# 12db-Xover.net
KiCad netlist of a schematic drawn in EAGLE
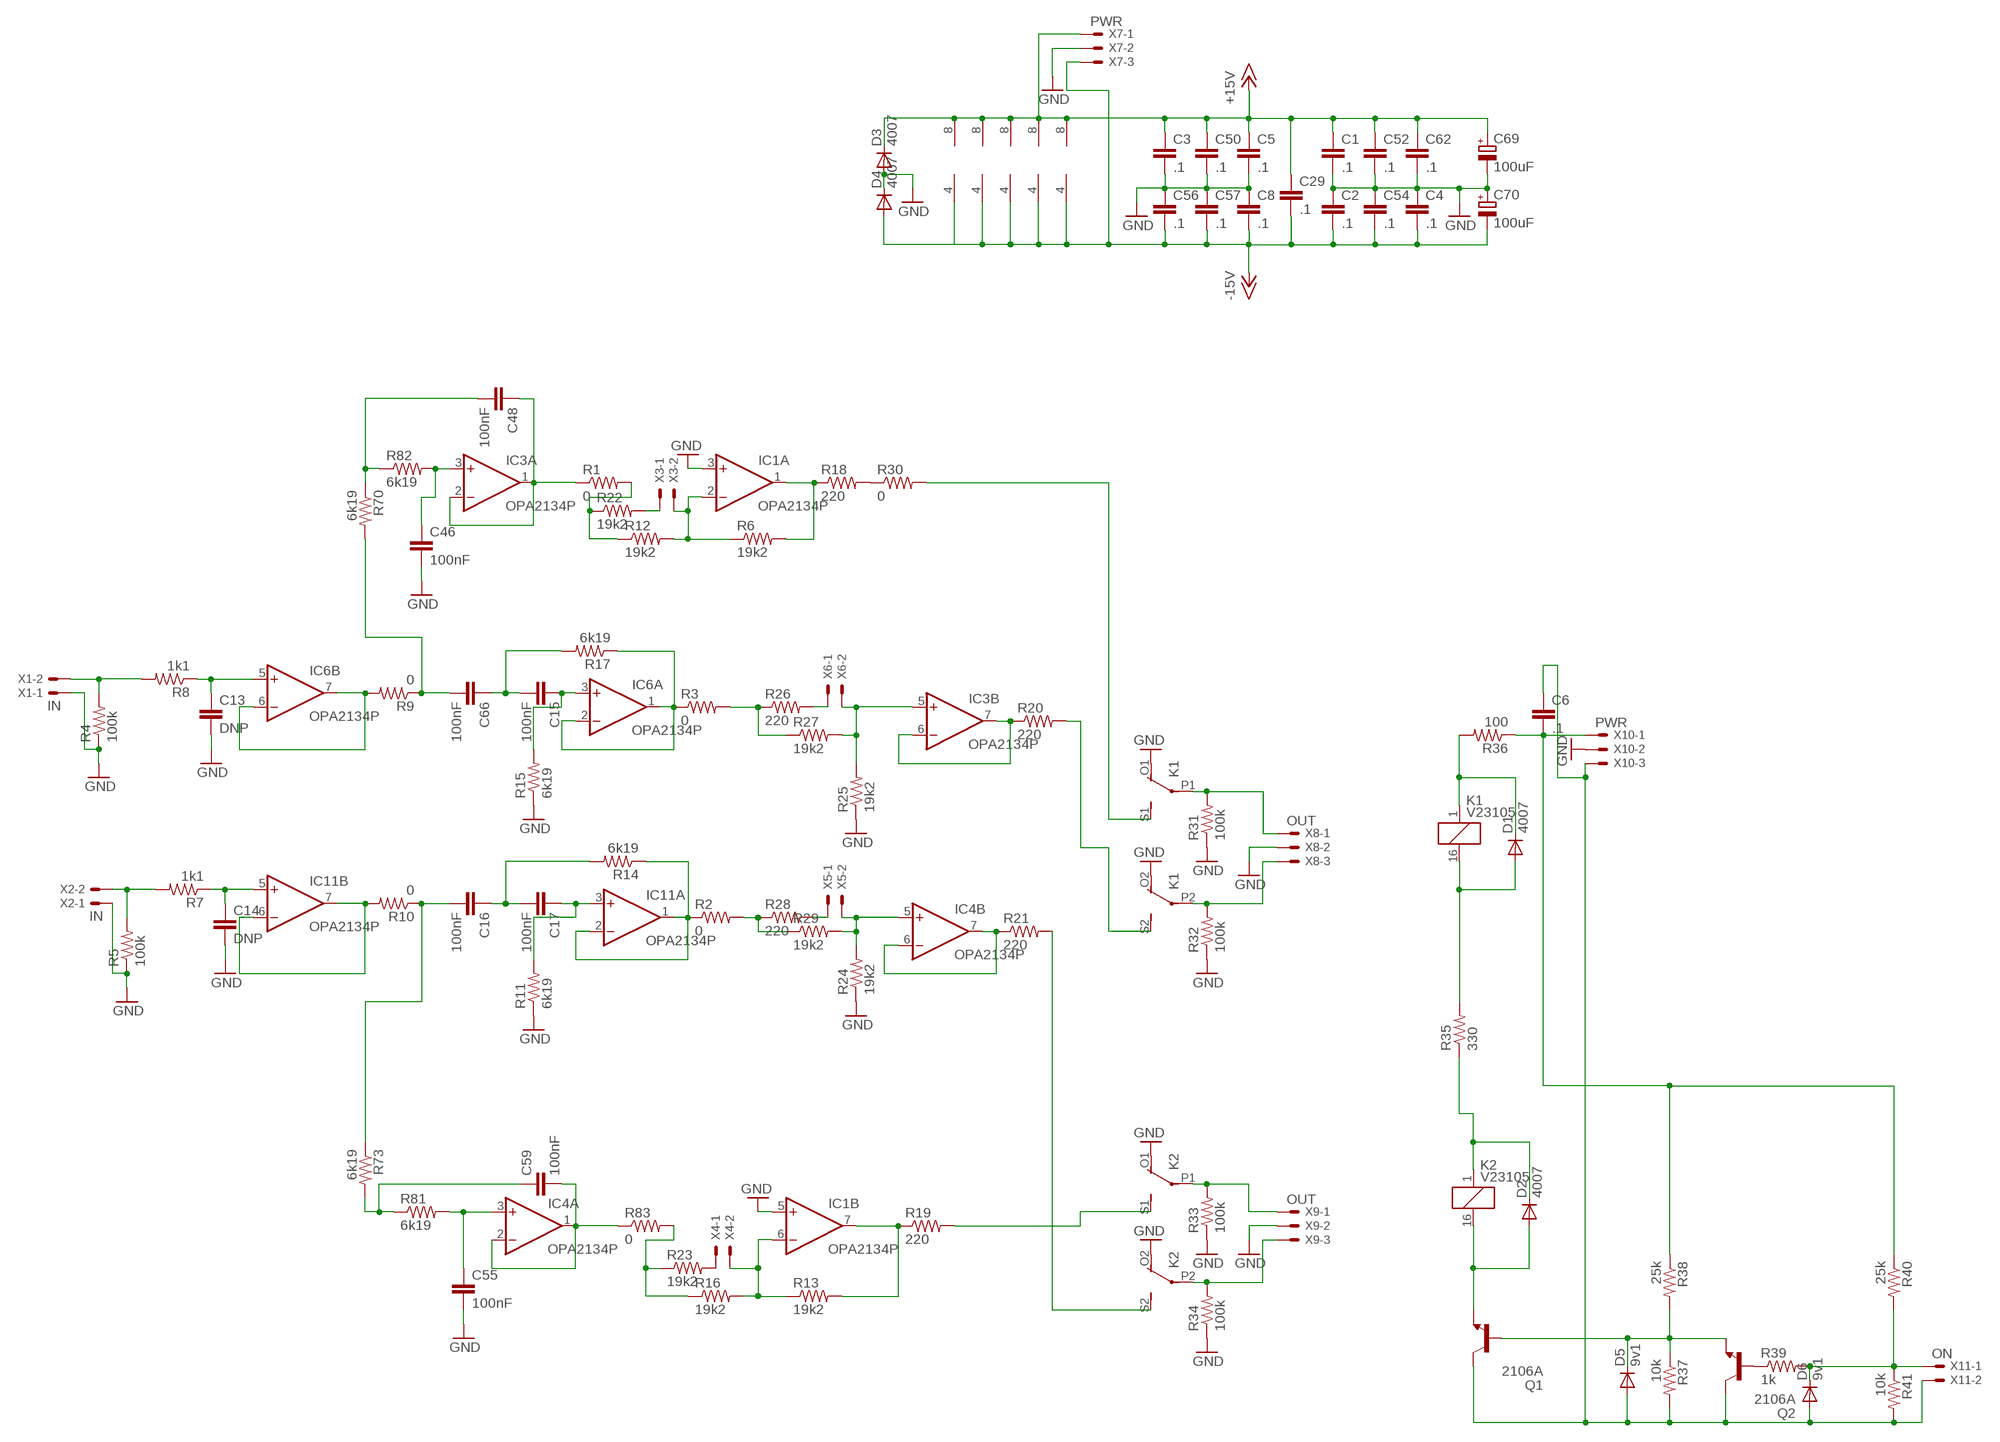
[diagram p0: schematic, sheet 1]

(export (version "E")
  (design (tool "Eeschema 10.0.6"))
  (components
    (comp (ref "C1")
      (value ".1")
      (footprint "eagle-import:C4532")
      (libsource (lib "eagle-import") (part "C-EUC4532"))
    )
    (comp (ref "C2")
      (value ".1")
      (footprint "eagle-import:C4532")
      (libsource (lib "eagle-import") (part "C-EUC4532"))
    )
    (comp (ref "C3")
      (value ".1")
      (footprint "eagle-import:C4532")
      (libsource (lib "eagle-import") (part "C-EUC4532"))
    )
    (comp (ref "C4")
      (value ".1")
      (footprint "eagle-import:C4532")
      (libsource (lib "eagle-import") (part "C-EUC4532"))
    )
    (comp (ref "C5")
      (value ".1")
      (footprint "eagle-import:C4532")
      (libsource (lib "eagle-import") (part "C-EUC4532"))
    )
    (comp (ref "C6")
      (value ".1")
      (footprint "eagle-import:C4532")
      (libsource (lib "eagle-import") (part "C-EUC4532"))
    )
    (comp (ref "C8")
      (value ".1")
      (footprint "eagle-import:C4532")
      (libsource (lib "eagle-import") (part "C-EUC4532"))
    )
    (comp (ref "C13")
      (value "DNP")
      (footprint "eagle-import:C050-035X075")
      (libsource (lib "eagle-import") (part "C-EU050-035X075"))
    )
    (comp (ref "C14")
      (value "DNP")
      (footprint "eagle-import:C050-035X075")
      (libsource (lib "eagle-import") (part "C-EU050-035X075"))
    )
    (comp (ref "C15")
      (value "100nF")
      (footprint "eagle-import:C050-075X075")
      (libsource (lib "eagle-import") (part "C-EU050-075X075"))
    )
    (comp (ref "C16")
      (value "100nF")
      (footprint "eagle-import:C050-075X075")
      (libsource (lib "eagle-import") (part "C-EU050-075X075"))
    )
    (comp (ref "C17")
      (value "100nF")
      (footprint "eagle-import:C050-075X075")
      (libsource (lib "eagle-import") (part "C-EU050-075X075"))
    )
    (comp (ref "C29")
      (value ".1")
      (footprint "eagle-import:C4532")
      (libsource (lib "eagle-import") (part "C-EUC4532"))
    )
    (comp (ref "C46")
      (value "100nF")
      (footprint "eagle-import:C050-075X075")
      (libsource (lib "eagle-import") (part "C-EU050-075X075"))
    )
    (comp (ref "C48")
      (value "100nF")
      (footprint "eagle-import:C050-075X075")
      (libsource (lib "eagle-import") (part "C-EU050-075X075"))
    )
    (comp (ref "C50")
      (value ".1")
      (footprint "eagle-import:C4532")
      (libsource (lib "eagle-import") (part "C-EUC4532"))
    )
    (comp (ref "C52")
      (value ".1")
      (footprint "eagle-import:C4532")
      (libsource (lib "eagle-import") (part "C-EUC4532"))
    )
    (comp (ref "C54")
      (value ".1")
      (footprint "eagle-import:C4532")
      (libsource (lib "eagle-import") (part "C-EUC4532"))
    )
    (comp (ref "C55")
      (value "100nF")
      (footprint "eagle-import:C050-075X075")
      (libsource (lib "eagle-import") (part "C-EU050-075X075"))
    )
    (comp (ref "C56")
      (value ".1")
      (footprint "eagle-import:C4532")
      (libsource (lib "eagle-import") (part "C-EUC4532"))
    )
    (comp (ref "C57")
      (value ".1")
      (footprint "eagle-import:C4532")
      (libsource (lib "eagle-import") (part "C-EUC4532"))
    )
    (comp (ref "C59")
      (value "100nF")
      (footprint "eagle-import:C050-075X075")
      (libsource (lib "eagle-import") (part "C-EU050-075X075"))
    )
    (comp (ref "C62")
      (value ".1")
      (footprint "eagle-import:C4532")
      (libsource (lib "eagle-import") (part "C-EUC4532"))
    )
    (comp (ref "C66")
      (value "100nF")
      (footprint "eagle-import:C050-075X075")
      (libsource (lib "eagle-import") (part "C-EU050-075X075"))
    )
    (comp (ref "C69")
      (value "100uF")
      (footprint "eagle-import:E3,5-10")
      (libsource (lib "eagle-import") (part "CPOL-EUE3.5-10"))
    )
    (comp (ref "C70")
      (value "100uF")
      (footprint "eagle-import:E3,5-10")
      (libsource (lib "eagle-import") (part "CPOL-EUE3.5-10"))
    )
    (comp (ref "D1")
      (value "4007")
      (footprint "eagle-import:DO35-10")
      (libsource (lib "eagle-import") (part "1N4148DO35-10"))
    )
    (comp (ref "D2")
      (value "4007")
      (footprint "eagle-import:DO35-10")
      (libsource (lib "eagle-import") (part "1N4148DO35-10"))
    )
    (comp (ref "D3")
      (value "4007")
      (footprint "eagle-import:DO35-10")
      (libsource (lib "eagle-import") (part "1N4148DO35-10"))
    )
    (comp (ref "D4")
      (value "4007")
      (footprint "eagle-import:DO35-10")
      (libsource (lib "eagle-import") (part "1N4148DO35-10"))
    )
    (comp (ref "D5")
      (value "9v1")
      (footprint "eagle-import:DO35-7")
      (libsource (lib "eagle-import") (part "1N4148DO35-7"))
    )
    (comp (ref "D6")
      (value "9v1")
      (footprint "eagle-import:DO35-7")
      (libsource (lib "eagle-import") (part "1N4148DO35-7"))
    )
    (comp (ref "IC1")
      (value "OPA2134P")
      (footprint "eagle-import:DIL08")
      (libsource (lib "eagle-import") (part "OPA2134P"))
    )
    (comp (ref "IC3")
      (value "OPA2134P")
      (footprint "eagle-import:DIL08")
      (libsource (lib "eagle-import") (part "OPA2134P"))
    )
    (comp (ref "IC4")
      (value "OPA2134P")
      (footprint "eagle-import:DIL08")
      (libsource (lib "eagle-import") (part "OPA2134P"))
    )
    (comp (ref "IC6")
      (value "OPA2134P")
      (footprint "eagle-import:DIL08")
      (libsource (lib "eagle-import") (part "OPA2134P"))
    )
    (comp (ref "IC11")
      (value "OPA2134P")
      (footprint "eagle-import:DIL08")
      (libsource (lib "eagle-import") (part "OPA2134P"))
    )
    (comp (ref "K1")
      (value "V23105")
      (footprint "eagle-import:351")
      (libsource (lib "eagle-import") (part "351"))
    )
    (comp (ref "K2")
      (value "V23105")
      (footprint "eagle-import:351")
      (libsource (lib "eagle-import") (part "351"))
    )
    (comp (ref "Q1")
      (value "2106A")
      (footprint "eagle-import:TO92-EBC")
      (libsource (lib "eagle-import") (part "BC546B"))
    )
    (comp (ref "Q2")
      (value "2106A")
      (footprint "eagle-import:TO92-EBC")
      (libsource (lib "eagle-import") (part "BC546B"))
    )
    (comp (ref "R1")
      (value "0")
      (footprint "eagle-import:0309_12")
      (libsource (lib "eagle-import") (part "R-US_0309/12"))
    )
    (comp (ref "R2")
      (value "0")
      (footprint "eagle-import:0309_10")
      (libsource (lib "eagle-import") (part "R-US_0309/10"))
    )
    (comp (ref "R3")
      (value "0")
      (footprint "eagle-import:0309_12")
      (libsource (lib "eagle-import") (part "R-US_0309/12"))
    )
    (comp (ref "R4")
      (value "100k")
      (footprint "eagle-import:0309_10")
      (libsource (lib "eagle-import") (part "R-US_0309/10"))
    )
    (comp (ref "R5")
      (value "100k")
      (footprint "eagle-import:0309_10")
      (libsource (lib "eagle-import") (part "R-US_0309/10"))
    )
    (comp (ref "R6")
      (value "19k2")
      (footprint "eagle-import:0309_10")
      (libsource (lib "eagle-import") (part "R-US_0309/10"))
    )
    (comp (ref "R7")
      (value "1k1")
      (footprint "eagle-import:0309_10")
      (libsource (lib "eagle-import") (part "R-US_0309/10"))
    )
    (comp (ref "R8")
      (value "1k1")
      (footprint "eagle-import:0309_10")
      (libsource (lib "eagle-import") (part "R-US_0309/10"))
    )
    (comp (ref "R9")
      (value "0")
      (footprint "eagle-import:0309_10")
      (libsource (lib "eagle-import") (part "R-US_0309/10"))
    )
    (comp (ref "R10")
      (value "0")
      (footprint "eagle-import:0309_10")
      (libsource (lib "eagle-import") (part "R-US_0309/10"))
    )
    (comp (ref "R11")
      (value "6k19")
      (footprint "eagle-import:0309_12")
      (libsource (lib "eagle-import") (part "R-US_0309/12"))
    )
    (comp (ref "R12")
      (value "19k2")
      (footprint "eagle-import:0309_10")
      (libsource (lib "eagle-import") (part "R-US_0309/10"))
    )
    (comp (ref "R13")
      (value "19k2")
      (footprint "eagle-import:0309_10")
      (libsource (lib "eagle-import") (part "R-US_0309/10"))
    )
    (comp (ref "R14")
      (value "6k19")
      (footprint "eagle-import:0309_10")
      (libsource (lib "eagle-import") (part "R-US_0309/10"))
    )
    (comp (ref "R15")
      (value "6k19")
      (footprint "eagle-import:0309_12")
      (libsource (lib "eagle-import") (part "R-US_0309/12"))
    )
    (comp (ref "R16")
      (value "19k2")
      (footprint "eagle-import:0309_10")
      (libsource (lib "eagle-import") (part "R-US_0309/10"))
    )
    (comp (ref "R17")
      (value "6k19")
      (footprint "eagle-import:0309_10")
      (libsource (lib "eagle-import") (part "R-US_0309/10"))
    )
    (comp (ref "R18")
      (value "220")
      (footprint "eagle-import:0309_12")
      (libsource (lib "eagle-import") (part "R-US_0309/12"))
    )
    (comp (ref "R19")
      (value "220")
      (footprint "eagle-import:0309_10")
      (libsource (lib "eagle-import") (part "R-US_0309/10"))
    )
    (comp (ref "R20")
      (value "220")
      (footprint "eagle-import:0309_12")
      (libsource (lib "eagle-import") (part "R-US_0309/12"))
    )
    (comp (ref "R21")
      (value "220")
      (footprint "eagle-import:0309_10")
      (libsource (lib "eagle-import") (part "R-US_0309/10"))
    )
    (comp (ref "R22")
      (value "19k2")
      (footprint "eagle-import:0309_10")
      (libsource (lib "eagle-import") (part "R-US_0309/10"))
    )
    (comp (ref "R23")
      (value "19k2")
      (footprint "eagle-import:0309_10")
      (libsource (lib "eagle-import") (part "R-US_0309/10"))
    )
    (comp (ref "R24")
      (value "19k2")
      (footprint "eagle-import:0309_12")
      (libsource (lib "eagle-import") (part "R-US_0309/12"))
    )
    (comp (ref "R25")
      (value "19k2")
      (footprint "eagle-import:0309_12")
      (libsource (lib "eagle-import") (part "R-US_0309/12"))
    )
    (comp (ref "R26")
      (value "220")
      (footprint "eagle-import:0309_10")
      (libsource (lib "eagle-import") (part "R-US_0309/10"))
    )
    (comp (ref "R27")
      (value "19k2")
      (footprint "eagle-import:0309_10")
      (libsource (lib "eagle-import") (part "R-US_0309/10"))
    )
    (comp (ref "R28")
      (value "220")
      (footprint "eagle-import:0309_10")
      (libsource (lib "eagle-import") (part "R-US_0309/10"))
    )
    (comp (ref "R29")
      (value "19k2")
      (footprint "eagle-import:0309_10")
      (libsource (lib "eagle-import") (part "R-US_0309/10"))
    )
    (comp (ref "R30")
      (value "0")
      (footprint "eagle-import:0309_10")
      (libsource (lib "eagle-import") (part "R-US_0309/10"))
    )
    (comp (ref "R31")
      (value "100k")
      (footprint "eagle-import:0309_10")
      (libsource (lib "eagle-import") (part "R-US_0309/10"))
    )
    (comp (ref "R32")
      (value "100k")
      (footprint "eagle-import:0309_10")
      (libsource (lib "eagle-import") (part "R-US_0309/10"))
    )
    (comp (ref "R33")
      (value "100k")
      (footprint "eagle-import:0309_10")
      (libsource (lib "eagle-import") (part "R-US_0309/10"))
    )
    (comp (ref "R34")
      (value "100k")
      (footprint "eagle-import:0309_10")
      (libsource (lib "eagle-import") (part "R-US_0309/10"))
    )
    (comp (ref "R35")
      (value "330")
      (footprint "eagle-import:0411_15")
      (libsource (lib "eagle-import") (part "R-US_0411/15"))
    )
    (comp (ref "R36")
      (value "100")
      (footprint "eagle-import:0309_12")
      (libsource (lib "eagle-import") (part "R-US_0309/12"))
    )
    (comp (ref "R37")
      (value "10k")
      (footprint "eagle-import:0309_12")
      (libsource (lib "eagle-import") (part "R-US_0309/12"))
    )
    (comp (ref "R38")
      (value "25k")
      (footprint "eagle-import:0309_10")
      (libsource (lib "eagle-import") (part "R-US_0309/10"))
    )
    (comp (ref "R39")
      (value "1k")
      (footprint "eagle-import:0309_10")
      (libsource (lib "eagle-import") (part "R-US_0309/10"))
    )
    (comp (ref "R40")
      (value "25k")
      (footprint "eagle-import:0309_10")
      (libsource (lib "eagle-import") (part "R-US_0309/10"))
    )
    (comp (ref "R41")
      (value "10k")
      (footprint "eagle-import:0309_12")
      (libsource (lib "eagle-import") (part "R-US_0309/12"))
    )
    (comp (ref "R70")
      (value "6k19")
      (footprint "eagle-import:0309_12")
      (libsource (lib "eagle-import") (part "R-US_0309/12"))
    )
    (comp (ref "R73")
      (value "6k19")
      (footprint "eagle-import:0309_12")
      (libsource (lib "eagle-import") (part "R-US_0309/12"))
    )
    (comp (ref "R81")
      (value "6k19")
      (footprint "eagle-import:0309_12")
      (libsource (lib "eagle-import") (part "R-US_0309/12"))
    )
    (comp (ref "R82")
      (value "6k19")
      (footprint "eagle-import:0309_12")
      (libsource (lib "eagle-import") (part "R-US_0309/12"))
    )
    (comp (ref "R83")
      (value "0")
      (footprint "eagle-import:0309_10")
      (libsource (lib "eagle-import") (part "R-US_0309/10"))
    )
    (comp (ref "X1")
      (value "IN")
      (footprint "eagle-import:22-23-2021")
      (fields (field (name "MF") "MOLEX") (field (name "MPN") "22-23-2021"))
      (libsource (lib "eagle-import") (part "22-23-2021"))
    )
    (comp (ref "X2")
      (value "IN")
      (footprint "eagle-import:22-23-2021")
      (fields (field (name "MF") "MOLEX") (field (name "MPN") "22-23-2021"))
      (libsource (lib "eagle-import") (part "22-23-2021"))
    )
    (comp (ref "X3")
      (value "22-23-2021")
      (footprint "eagle-import:22-23-2021")
      (fields (field (name "MF") "MOLEX"))
      (libsource (lib "eagle-import") (part "22-23-2021"))
    )
    (comp (ref "X4")
      (value "22-23-2021")
      (footprint "eagle-import:22-23-2021")
      (fields (field (name "MF") "MOLEX"))
      (libsource (lib "eagle-import") (part "22-23-2021"))
    )
    (comp (ref "X5")
      (value "22-23-2021")
      (footprint "eagle-import:22-23-2021")
      (fields (field (name "MF") "MOLEX"))
      (libsource (lib "eagle-import") (part "22-23-2021"))
    )
    (comp (ref "X6")
      (value "22-23-2021")
      (footprint "eagle-import:22-23-2021")
      (fields (field (name "MF") "MOLEX"))
      (libsource (lib "eagle-import") (part "22-23-2021"))
    )
    (comp (ref "X7")
      (value "PWR")
      (footprint "eagle-import:22-23-2031")
      (fields (field (name "MF") "MOLEX") (field (name "MPN") "22-23-2031"))
      (libsource (lib "eagle-import") (part "22-23-2031"))
    )
    (comp (ref "X8")
      (value "OUT")
      (footprint "eagle-import:22-23-2031")
      (fields (field (name "MF") "MOLEX") (field (name "MPN") "22-23-2031"))
      (libsource (lib "eagle-import") (part "22-23-2031"))
    )
    (comp (ref "X9")
      (value "OUT")
      (footprint "eagle-import:22-23-2031")
      (fields (field (name "MF") "MOLEX") (field (name "MPN") "22-23-2031"))
      (libsource (lib "eagle-import") (part "22-23-2031"))
    )
    (comp (ref "X10")
      (value "PWR")
      (footprint "eagle-import:22-23-2031")
      (fields (field (name "MF") "MOLEX") (field (name "MPN") "22-23-2031"))
      (libsource (lib "eagle-import") (part "22-23-2031"))
    )
    (comp (ref "X11")
      (value "ON")
      (footprint "eagle-import:22-23-2021")
      (fields (field (name "MF") "MOLEX") (field (name "MPN") "22-23-2021"))
      (libsource (lib "eagle-import") (part "22-23-2021"))
    )
  )
  (nets
    (net (code "1") (name "+15V") (class "Default")
      (node (ref "C1") (pin "1") (pinfunction "1_1") (pintype "passive"))
      (node (ref "C29") (pin "1") (pinfunction "1_1") (pintype "passive"))
      (node (ref "C3") (pin "1") (pinfunction "1_1") (pintype "passive"))
      (node (ref "C5") (pin "1") (pinfunction "1_1") (pintype "passive"))
      (node (ref "C50") (pin "1") (pinfunction "1_1") (pintype "passive"))
      (node (ref "C52") (pin "1") (pinfunction "1_1") (pintype "passive"))
      (node (ref "C62") (pin "1") (pinfunction "1_1") (pintype "passive"))
      (node (ref "C69") (pin "+") (pinfunction "+_+") (pintype "passive"))
      (node (ref "D3") (pin "C") (pinfunction "C_C") (pintype "passive"))
      (node (ref "IC1") (pin "8") (pinfunction "V+_8") (pintype "power_in"))
      (node (ref "IC11") (pin "8") (pinfunction "V+_8") (pintype "power_in"))
      (node (ref "IC3") (pin "8") (pinfunction "V+_8") (pintype "power_in"))
      (node (ref "IC4") (pin "8") (pinfunction "V+_8") (pintype "power_in"))
      (node (ref "IC6") (pin "8") (pinfunction "V+_8") (pintype "power_in"))
      (node (ref "X7") (pin "1") (pinfunction "S_1") (pintype "passive"))
    )
    (net (code "2") (name "-15V") (class "Default")
      (node (ref "C2") (pin "2") (pinfunction "2_2") (pintype "passive"))
      (node (ref "C29") (pin "2") (pinfunction "2_2") (pintype "passive"))
      (node (ref "C4") (pin "2") (pinfunction "2_2") (pintype "passive"))
      (node (ref "C54") (pin "2") (pinfunction "2_2") (pintype "passive"))
      (node (ref "C56") (pin "2") (pinfunction "2_2") (pintype "passive"))
      (node (ref "C57") (pin "2") (pinfunction "2_2") (pintype "passive"))
      (node (ref "C70") (pin "-") (pinfunction "-_-") (pintype "passive"))
      (node (ref "C8") (pin "2") (pinfunction "2_2") (pintype "passive"))
      (node (ref "D4") (pin "A") (pinfunction "A_A") (pintype "passive"))
      (node (ref "IC1") (pin "4") (pinfunction "V-_4") (pintype "power_in"))
      (node (ref "IC11") (pin "4") (pinfunction "V-_4") (pintype "power_in"))
      (node (ref "IC3") (pin "4") (pinfunction "V-_4") (pintype "power_in"))
      (node (ref "IC4") (pin "4") (pinfunction "V-_4") (pintype "power_in"))
      (node (ref "IC6") (pin "4") (pinfunction "V-_4") (pintype "power_in"))
      (node (ref "X7") (pin "3") (pinfunction "S_3") (pintype "passive"))
    )
    (net (code "3") (name "GND") (class "Default")
      (node (ref "C1") (pin "2") (pinfunction "2_2") (pintype "passive"))
      (node (ref "C13") (pin "2") (pinfunction "2_2") (pintype "passive"))
      (node (ref "C14") (pin "2") (pinfunction "2_2") (pintype "passive"))
      (node (ref "C2") (pin "1") (pinfunction "1_1") (pintype "passive"))
      (node (ref "C3") (pin "2") (pinfunction "2_2") (pintype "passive"))
      (node (ref "C4") (pin "1") (pinfunction "1_1") (pintype "passive"))
      (node (ref "C46") (pin "2") (pinfunction "2_2") (pintype "passive"))
      (node (ref "C5") (pin "2") (pinfunction "2_2") (pintype "passive"))
      (node (ref "C50") (pin "2") (pinfunction "2_2") (pintype "passive"))
      (node (ref "C52") (pin "2") (pinfunction "2_2") (pintype "passive"))
      (node (ref "C54") (pin "1") (pinfunction "1_1") (pintype "passive"))
      (node (ref "C55") (pin "2") (pinfunction "2_2") (pintype "passive"))
      (node (ref "C56") (pin "1") (pinfunction "1_1") (pintype "passive"))
      (node (ref "C57") (pin "1") (pinfunction "1_1") (pintype "passive"))
      (node (ref "C62") (pin "2") (pinfunction "2_2") (pintype "passive"))
      (node (ref "C69") (pin "-") (pinfunction "-_-") (pintype "passive"))
      (node (ref "C70") (pin "+") (pinfunction "+_+") (pintype "passive"))
      (node (ref "C8") (pin "1") (pinfunction "1_1") (pintype "passive"))
      (node (ref "D3") (pin "A") (pinfunction "A_A") (pintype "passive"))
      (node (ref "D4") (pin "C") (pinfunction "C_C") (pintype "passive"))
      (node (ref "IC1") (pin "3") (pinfunction "+IN_3") (pintype "input"))
      (node (ref "IC1") (pin "5") (pinfunction "+IN_5") (pintype "input"))
      (node (ref "K1") (pin "O1") (pinfunction "O_O1") (pintype "passive"))
      (node (ref "K1") (pin "O2") (pinfunction "O_O2") (pintype "passive"))
      (node (ref "K2") (pin "O1") (pinfunction "O_O1") (pintype "passive"))
      (node (ref "K2") (pin "O2") (pinfunction "O_O2") (pintype "passive"))
      (node (ref "R11") (pin "1") (pinfunction "1_1") (pintype "passive"))
      (node (ref "R15") (pin "1") (pinfunction "1_1") (pintype "passive"))
      (node (ref "R24") (pin "1") (pinfunction "1_1") (pintype "passive"))
      (node (ref "R25") (pin "1") (pinfunction "1_1") (pintype "passive"))
      (node (ref "R31") (pin "1") (pinfunction "1_1") (pintype "passive"))
      (node (ref "R32") (pin "1") (pinfunction "1_1") (pintype "passive"))
      (node (ref "R33") (pin "1") (pinfunction "1_1") (pintype "passive"))
      (node (ref "R34") (pin "1") (pinfunction "1_1") (pintype "passive"))
      (node (ref "R4") (pin "1") (pinfunction "1_1") (pintype "passive"))
      (node (ref "R5") (pin "1") (pinfunction "1_1") (pintype "passive"))
      (node (ref "X1") (pin "1") (pinfunction "S_1") (pintype "passive"))
      (node (ref "X10") (pin "2") (pinfunction "S_2") (pintype "passive"))
      (node (ref "X2") (pin "1") (pinfunction "S_1") (pintype "passive"))
      (node (ref "X7") (pin "2") (pinfunction "S_2") (pintype "passive"))
      (node (ref "X8") (pin "2") (pinfunction "S_2") (pintype "passive"))
      (node (ref "X9") (pin "2") (pinfunction "S_2") (pintype "passive"))
    )
    (net (code "4") (name "Net-(C15-Pad2)") (class "Default")
      (node (ref "C15") (pin "2") (pinfunction "2_2") (pintype "passive"))
      (node (ref "C66") (pin "1") (pinfunction "1_1") (pintype "passive"))
      (node (ref "R17") (pin "2") (pinfunction "2_2") (pintype "passive"))
    )
    (net (code "5") (name "Net-(C16-Pad1)") (class "Default")
      (node (ref "C16") (pin "1") (pinfunction "1_1") (pintype "passive"))
      (node (ref "C17") (pin "2") (pinfunction "2_2") (pintype "passive"))
      (node (ref "R14") (pin "2") (pinfunction "2_2") (pintype "passive"))
    )
    (net (code "6") (name "Net-(C16-Pad2)") (class "Default")
      (node (ref "C16") (pin "2") (pinfunction "2_2") (pintype "passive"))
      (node (ref "R10") (pin "1") (pinfunction "1_1") (pintype "passive"))
      (node (ref "R73") (pin "1") (pinfunction "1_1") (pintype "passive"))
    )
    (net (code "7") (name "Net-(C48-Pad2)") (class "Default")
      (node (ref "C48") (pin "2") (pinfunction "2_2") (pintype "passive"))
      (node (ref "R70") (pin "1") (pinfunction "1_1") (pintype "passive"))
      (node (ref "R82") (pin "1") (pinfunction "1_1") (pintype "passive"))
    )
    (net (code "8") (name "Net-(C59-Pad1)") (class "Default")
      (node (ref "C59") (pin "1") (pinfunction "1_1") (pintype "passive"))
      (node (ref "R73") (pin "2") (pinfunction "2_2") (pintype "passive"))
      (node (ref "R81") (pin "1") (pinfunction "1_1") (pintype "passive"))
    )
    (net (code "9") (name "Net-(C66-Pad2)") (class "Default")
      (node (ref "C66") (pin "2") (pinfunction "2_2") (pintype "passive"))
      (node (ref "R70") (pin "2") (pinfunction "2_2") (pintype "passive"))
      (node (ref "R9") (pin "1") (pinfunction "1_1") (pintype "passive"))
    )
    (net (code "10") (name "Net-(D1-PadC)") (class "Default")
      (node (ref "D1") (pin "C") (pinfunction "C_C") (pintype "passive"))
      (node (ref "K1") (pin "1") (pinfunction "1_1") (pintype "passive"))
      (node (ref "R36") (pin "2") (pinfunction "2_2") (pintype "passive"))
    )
    (net (code "11") (name "Net-(D2-PadC)") (class "Default")
      (node (ref "D2") (pin "C") (pinfunction "C_C") (pintype "passive"))
      (node (ref "K2") (pin "1") (pinfunction "1_1") (pintype "passive"))
      (node (ref "R35") (pin "1") (pinfunction "1_1") (pintype "passive"))
    )
    (net (code "12") (name "Net-(D5-PadC)") (class "Default")
      (node (ref "D5") (pin "C") (pinfunction "C_C") (pintype "passive"))
      (node (ref "Q1") (pin "B") (pinfunction "B_B") (pintype "passive"))
      (node (ref "Q2") (pin "E") (pinfunction "E_E") (pintype "passive"))
      (node (ref "R37") (pin "1") (pinfunction "1_1") (pintype "passive"))
      (node (ref "R38") (pin "2") (pinfunction "2_2") (pintype "passive"))
    )
    (net (code "13") (name "Net-(IC1A--IN)") (class "Default")
      (node (ref "IC1") (pin "2") (pinfunction "-IN_2") (pintype "input"))
      (node (ref "R12") (pin "2") (pinfunction "2_2") (pintype "passive"))
      (node (ref "R6") (pin "1") (pinfunction "1_1") (pintype "passive"))
      (node (ref "X3") (pin "2") (pinfunction "S_2") (pintype "passive"))
    )
    (net (code "14") (name "Net-(IC1A-OUT)") (class "Default")
      (node (ref "IC1") (pin "1") (pinfunction "OUT_1") (pintype "output"))
      (node (ref "R18") (pin "1") (pinfunction "1_1") (pintype "passive"))
      (node (ref "R6") (pin "2") (pinfunction "2_2") (pintype "passive"))
    )
    (net (code "15") (name "Net-(IC1B--IN)") (class "Default")
      (node (ref "IC1") (pin "6") (pinfunction "-IN_6") (pintype "input"))
      (node (ref "R13") (pin "1") (pinfunction "1_1") (pintype "passive"))
      (node (ref "R16") (pin "2") (pinfunction "2_2") (pintype "passive"))
      (node (ref "X4") (pin "2") (pinfunction "S_2") (pintype "passive"))
    )
    (net (code "16") (name "Net-(IC1B-OUT)") (class "Default")
      (node (ref "IC1") (pin "7") (pinfunction "OUT_7") (pintype "output"))
      (node (ref "R13") (pin "2") (pinfunction "2_2") (pintype "passive"))
      (node (ref "R19") (pin "1") (pinfunction "1_1") (pintype "passive"))
    )
    (net (code "17") (name "Net-(IC3A-+IN)") (class "Default")
      (node (ref "C46") (pin "1") (pinfunction "1_1") (pintype "passive"))
      (node (ref "IC3") (pin "3") (pinfunction "+IN_3") (pintype "input"))
      (node (ref "R82") (pin "2") (pinfunction "2_2") (pintype "passive"))
    )
    (net (code "18") (name "Net-(IC3A--IN)") (class "Default")
      (node (ref "C48") (pin "1") (pinfunction "1_1") (pintype "passive"))
      (node (ref "IC3") (pin "1") (pinfunction "OUT_1") (pintype "output"))
      (node (ref "IC3") (pin "2") (pinfunction "-IN_2") (pintype "input"))
      (node (ref "R1") (pin "1") (pinfunction "1_1") (pintype "passive"))
    )
    (net (code "19") (name "Net-(IC3B-+IN)") (class "Default")
      (node (ref "IC3") (pin "5") (pinfunction "+IN_5") (pintype "input"))
      (node (ref "R25") (pin "2") (pinfunction "2_2") (pintype "passive"))
      (node (ref "R27") (pin "2") (pinfunction "2_2") (pintype "passive"))
      (node (ref "X6") (pin "2") (pinfunction "S_2") (pintype "passive"))
    )
    (net (code "20") (name "Net-(IC3B--IN)") (class "Default")
      (node (ref "IC3") (pin "6") (pinfunction "-IN_6") (pintype "input"))
      (node (ref "IC3") (pin "7") (pinfunction "OUT_7") (pintype "output"))
      (node (ref "R20") (pin "1") (pinfunction "1_1") (pintype "passive"))
    )
    (net (code "21") (name "Net-(IC4A-+IN)") (class "Default")
      (node (ref "C55") (pin "1") (pinfunction "1_1") (pintype "passive"))
      (node (ref "IC4") (pin "3") (pinfunction "+IN_3") (pintype "input"))
      (node (ref "R81") (pin "2") (pinfunction "2_2") (pintype "passive"))
    )
    (net (code "22") (name "Net-(IC4A--IN)") (class "Default")
      (node (ref "C59") (pin "2") (pinfunction "2_2") (pintype "passive"))
      (node (ref "IC4") (pin "1") (pinfunction "OUT_1") (pintype "output"))
      (node (ref "IC4") (pin "2") (pinfunction "-IN_2") (pintype "input"))
      (node (ref "R83") (pin "1") (pinfunction "1_1") (pintype "passive"))
    )
    (net (code "23") (name "Net-(IC4B-+IN)") (class "Default")
      (node (ref "IC4") (pin "5") (pinfunction "+IN_5") (pintype "input"))
      (node (ref "R24") (pin "2") (pinfunction "2_2") (pintype "passive"))
      (node (ref "R29") (pin "2") (pinfunction "2_2") (pintype "passive"))
      (node (ref "X5") (pin "2") (pinfunction "S_2") (pintype "passive"))
    )
    (net (code "24") (name "Net-(IC4B--IN)") (class "Default")
      (node (ref "IC4") (pin "6") (pinfunction "-IN_6") (pintype "input"))
      (node (ref "IC4") (pin "7") (pinfunction "OUT_7") (pintype "output"))
      (node (ref "R21") (pin "1") (pinfunction "1_1") (pintype "passive"))
    )
    (net (code "25") (name "Net-(IC6A-+IN)") (class "Default")
      (node (ref "C15") (pin "1") (pinfunction "1_1") (pintype "passive"))
      (node (ref "IC6") (pin "3") (pinfunction "+IN_3") (pintype "input"))
      (node (ref "R15") (pin "2") (pinfunction "2_2") (pintype "passive"))
    )
    (net (code "26") (name "Net-(IC6A--IN)") (class "Default")
      (node (ref "IC6") (pin "1") (pinfunction "OUT_1") (pintype "output"))
      (node (ref "IC6") (pin "2") (pinfunction "-IN_2") (pintype "input"))
      (node (ref "R17") (pin "1") (pinfunction "1_1") (pintype "passive"))
      (node (ref "R3") (pin "1") (pinfunction "1_1") (pintype "passive"))
    )
    (net (code "27") (name "Net-(IC6B-+IN)") (class "Default")
      (node (ref "C13") (pin "1") (pinfunction "1_1") (pintype "passive"))
      (node (ref "IC6") (pin "5") (pinfunction "+IN_5") (pintype "input"))
      (node (ref "R8") (pin "1") (pinfunction "1_1") (pintype "passive"))
    )
    (net (code "28") (name "Net-(IC6B--IN)") (class "Default")
      (node (ref "IC6") (pin "6") (pinfunction "-IN_6") (pintype "input"))
      (node (ref "IC6") (pin "7") (pinfunction "OUT_7") (pintype "output"))
      (node (ref "R9") (pin "2") (pinfunction "2_2") (pintype "passive"))
    )
    (net (code "29") (name "Net-(IC11A-+IN)") (class "Default")
      (node (ref "C17") (pin "1") (pinfunction "1_1") (pintype "passive"))
      (node (ref "IC11") (pin "3") (pinfunction "+IN_3") (pintype "input"))
      (node (ref "R11") (pin "2") (pinfunction "2_2") (pintype "passive"))
    )
    (net (code "30") (name "Net-(IC11A--IN)") (class "Default")
      (node (ref "IC11") (pin "1") (pinfunction "OUT_1") (pintype "output"))
      (node (ref "IC11") (pin "2") (pinfunction "-IN_2") (pintype "input"))
      (node (ref "R14") (pin "1") (pinfunction "1_1") (pintype "passive"))
      (node (ref "R2") (pin "1") (pinfunction "1_1") (pintype "passive"))
    )
    (net (code "31") (name "Net-(IC11B-+IN)") (class "Default")
      (node (ref "C14") (pin "1") (pinfunction "1_1") (pintype "passive"))
      (node (ref "IC11") (pin "5") (pinfunction "+IN_5") (pintype "input"))
      (node (ref "R7") (pin "1") (pinfunction "1_1") (pintype "passive"))
    )
    (net (code "32") (name "Net-(IC11B--IN)") (class "Default")
      (node (ref "IC11") (pin "6") (pinfunction "-IN_6") (pintype "input"))
      (node (ref "IC11") (pin "7") (pinfunction "OUT_7") (pintype "output"))
      (node (ref "R10") (pin "2") (pinfunction "2_2") (pintype "passive"))
    )
    (net (code "33") (name "Net-(K1A-2)") (class "Default")
      (node (ref "D1") (pin "A") (pinfunction "A_A") (pintype "passive"))
      (node (ref "K1") (pin "16") (pinfunction "2_16") (pintype "passive"))
      (node (ref "R35") (pin "2") (pinfunction "2_2") (pintype "passive"))
    )
    (net (code "34") (name "Net-(K1B-P)") (class "Default")
      (node (ref "K1") (pin "P1") (pinfunction "P_P1") (pintype "passive"))
      (node (ref "R31") (pin "2") (pinfunction "2_2") (pintype "passive"))
      (node (ref "X8") (pin "1") (pinfunction "S_1") (pintype "passive"))
    )
    (net (code "35") (name "Net-(K1B-S)") (class "Default")
      (node (ref "K1") (pin "S1") (pinfunction "S_S1") (pintype "passive"))
      (node (ref "R30") (pin "2") (pinfunction "2_2") (pintype "passive"))
    )
    (net (code "36") (name "Net-(K1C-P)") (class "Default")
      (node (ref "K1") (pin "P2") (pinfunction "P_P2") (pintype "passive"))
      (node (ref "R32") (pin "2") (pinfunction "2_2") (pintype "passive"))
      (node (ref "X8") (pin "3") (pinfunction "S_3") (pintype "passive"))
    )
    (net (code "37") (name "Net-(K1C-S)") (class "Default")
      (node (ref "K1") (pin "S2") (pinfunction "S_S2") (pintype "passive"))
      (node (ref "R20") (pin "2") (pinfunction "2_2") (pintype "passive"))
    )
    (net (code "38") (name "Net-(K2A-2)") (class "Default")
      (node (ref "D2") (pin "A") (pinfunction "A_A") (pintype "passive"))
      (node (ref "K2") (pin "16") (pinfunction "2_16") (pintype "passive"))
      (node (ref "Q1") (pin "E") (pinfunction "E_E") (pintype "passive"))
    )
    (net (code "39") (name "Net-(K2B-P)") (class "Default")
      (node (ref "K2") (pin "P1") (pinfunction "P_P1") (pintype "passive"))
      (node (ref "R33") (pin "2") (pinfunction "2_2") (pintype "passive"))
      (node (ref "X9") (pin "1") (pinfunction "S_1") (pintype "passive"))
    )
    (net (code "40") (name "Net-(K2B-S)") (class "Default")
      (node (ref "K2") (pin "S1") (pinfunction "S_S1") (pintype "passive"))
      (node (ref "R19") (pin "2") (pinfunction "2_2") (pintype "passive"))
    )
    (net (code "41") (name "Net-(K2C-P)") (class "Default")
      (node (ref "K2") (pin "P2") (pinfunction "P_P2") (pintype "passive"))
      (node (ref "R34") (pin "2") (pinfunction "2_2") (pintype "passive"))
      (node (ref "X9") (pin "3") (pinfunction "S_3") (pintype "passive"))
    )
    (net (code "42") (name "Net-(K2C-S)") (class "Default")
      (node (ref "K2") (pin "S2") (pinfunction "S_S2") (pintype "passive"))
      (node (ref "R21") (pin "2") (pinfunction "2_2") (pintype "passive"))
    )
    (net (code "43") (name "Net-(Q2-PadB)") (class "Default")
      (node (ref "Q2") (pin "B") (pinfunction "B_B") (pintype "passive"))
      (node (ref "R39") (pin "1") (pinfunction "1_1") (pintype "passive"))
    )
    (net (code "44") (name "Net-(R1-Pad2)") (class "Default")
      (node (ref "R1") (pin "2") (pinfunction "2_2") (pintype "passive"))
      (node (ref "R12") (pin "1") (pinfunction "1_1") (pintype "passive"))
      (node (ref "R22") (pin "1") (pinfunction "1_1") (pintype "passive"))
    )
    (net (code "45") (name "Net-(R2-Pad2)") (class "Default")
      (node (ref "R2") (pin "2") (pinfunction "2_2") (pintype "passive"))
      (node (ref "R28") (pin "1") (pinfunction "1_1") (pintype "passive"))
      (node (ref "R29") (pin "1") (pinfunction "1_1") (pintype "passive"))
    )
    (net (code "46") (name "Net-(R16-Pad1)") (class "Default")
      (node (ref "R16") (pin "1") (pinfunction "1_1") (pintype "passive"))
      (node (ref "R23") (pin "1") (pinfunction "1_1") (pintype "passive"))
      (node (ref "R83") (pin "2") (pinfunction "2_2") (pintype "passive"))
    )
    (net (code "47") (name "Net-(R18-Pad2)") (class "Default")
      (node (ref "R18") (pin "2") (pinfunction "2_2") (pintype "passive"))
      (node (ref "R30") (pin "1") (pinfunction "1_1") (pintype "passive"))
    )
    (net (code "48") (name "Net-(R26-Pad1)") (class "Default")
      (node (ref "R26") (pin "1") (pinfunction "1_1") (pintype "passive"))
      (node (ref "R27") (pin "1") (pinfunction "1_1") (pintype "passive"))
      (node (ref "R3") (pin "2") (pinfunction "2_2") (pintype "passive"))
    )
    (net (code "49") (name "Net-(X1B-S)") (class "Default")
      (node (ref "R4") (pin "2") (pinfunction "2_2") (pintype "passive"))
      (node (ref "R8") (pin "2") (pinfunction "2_2") (pintype "passive"))
      (node (ref "X1") (pin "2") (pinfunction "S_2") (pintype "passive"))
    )
    (net (code "50") (name "Net-(X2B-S)") (class "Default")
      (node (ref "R5") (pin "2") (pinfunction "2_2") (pintype "passive"))
      (node (ref "R7") (pin "2") (pinfunction "2_2") (pintype "passive"))
      (node (ref "X2") (pin "2") (pinfunction "S_2") (pintype "passive"))
    )
    (net (code "51") (name "Net-(X3A-S)") (class "Default")
      (node (ref "R22") (pin "2") (pinfunction "2_2") (pintype "passive"))
      (node (ref "X3") (pin "1") (pinfunction "S_1") (pintype "passive"))
    )
    (net (code "52") (name "Net-(X4A-S)") (class "Default")
      (node (ref "R23") (pin "2") (pinfunction "2_2") (pintype "passive"))
      (node (ref "X4") (pin "1") (pinfunction "S_1") (pintype "passive"))
    )
    (net (code "53") (name "Net-(X5A-S)") (class "Default")
      (node (ref "R28") (pin "2") (pinfunction "2_2") (pintype "passive"))
      (node (ref "X5") (pin "1") (pinfunction "S_1") (pintype "passive"))
    )
    (net (code "54") (name "Net-(X6A-S)") (class "Default")
      (node (ref "R26") (pin "2") (pinfunction "2_2") (pintype "passive"))
      (node (ref "X6") (pin "1") (pinfunction "S_1") (pintype "passive"))
    )
    (net (code "55") (name "Net-(X10A-S)") (class "Default")
      (node (ref "C6") (pin "2") (pinfunction "2_2") (pintype "passive"))
      (node (ref "R36") (pin "1") (pinfunction "1_1") (pintype "passive"))
      (node (ref "R38") (pin "1") (pinfunction "1_1") (pintype "passive"))
      (node (ref "R40") (pin "1") (pinfunction "1_1") (pintype "passive"))
      (node (ref "X10") (pin "1") (pinfunction "S_1") (pintype "passive"))
    )
    (net (code "56") (name "Net-(X10C-S)") (class "Default")
      (node (ref "C6") (pin "1") (pinfunction "1_1") (pintype "passive"))
      (node (ref "D5") (pin "A") (pinfunction "A_A") (pintype "passive"))
      (node (ref "D6") (pin "A") (pinfunction "A_A") (pintype "passive"))
      (node (ref "Q1") (pin "C") (pinfunction "C_C") (pintype "passive"))
      (node (ref "Q2") (pin "C") (pinfunction "C_C") (pintype "passive"))
      (node (ref "R37") (pin "2") (pinfunction "2_2") (pintype "passive"))
      (node (ref "R41") (pin "2") (pinfunction "2_2") (pintype "passive"))
      (node (ref "X10") (pin "3") (pinfunction "S_3") (pintype "passive"))
      (node (ref "X11") (pin "2") (pinfunction "S_2") (pintype "passive"))
    )
    (net (code "57") (name "Net-(X11A-S)") (class "Default")
      (node (ref "D6") (pin "C") (pinfunction "C_C") (pintype "passive"))
      (node (ref "R39") (pin "2") (pinfunction "2_2") (pintype "passive"))
      (node (ref "R40") (pin "2") (pinfunction "2_2") (pintype "passive"))
      (node (ref "R41") (pin "1") (pinfunction "1_1") (pintype "passive"))
      (node (ref "X11") (pin "1") (pinfunction "S_1") (pintype "passive"))
    )
  )
)
